# controller5Teensy.net
KiCad netlist of a schematic drawn in EAGLE
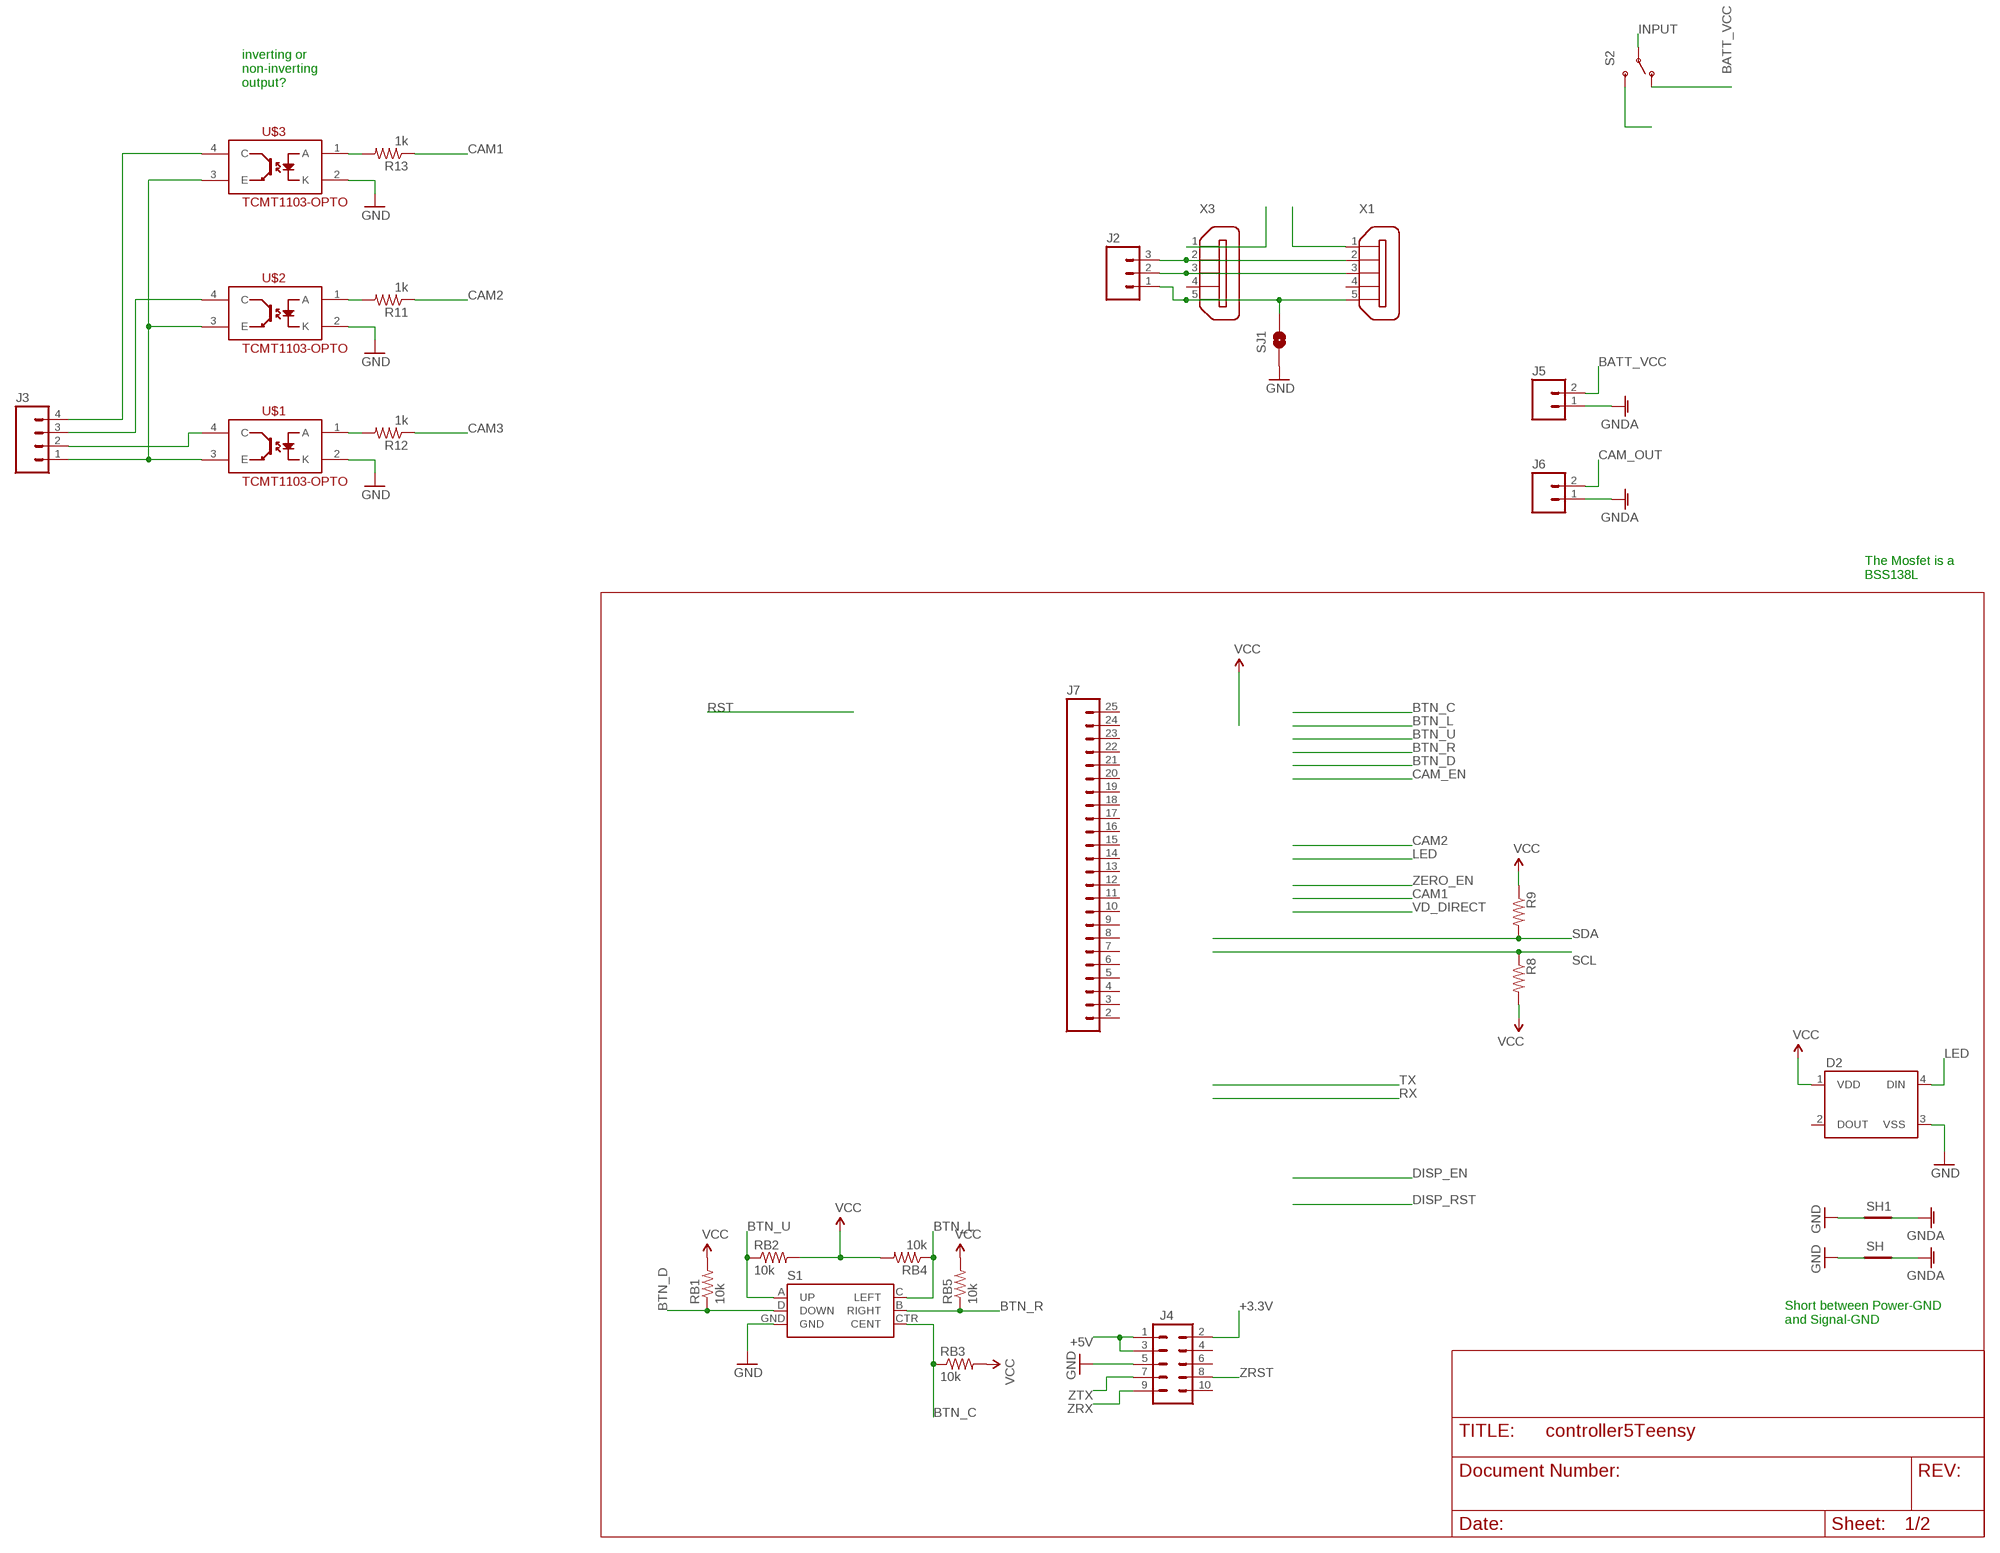
[diagram p0: schematic, sheet 1]
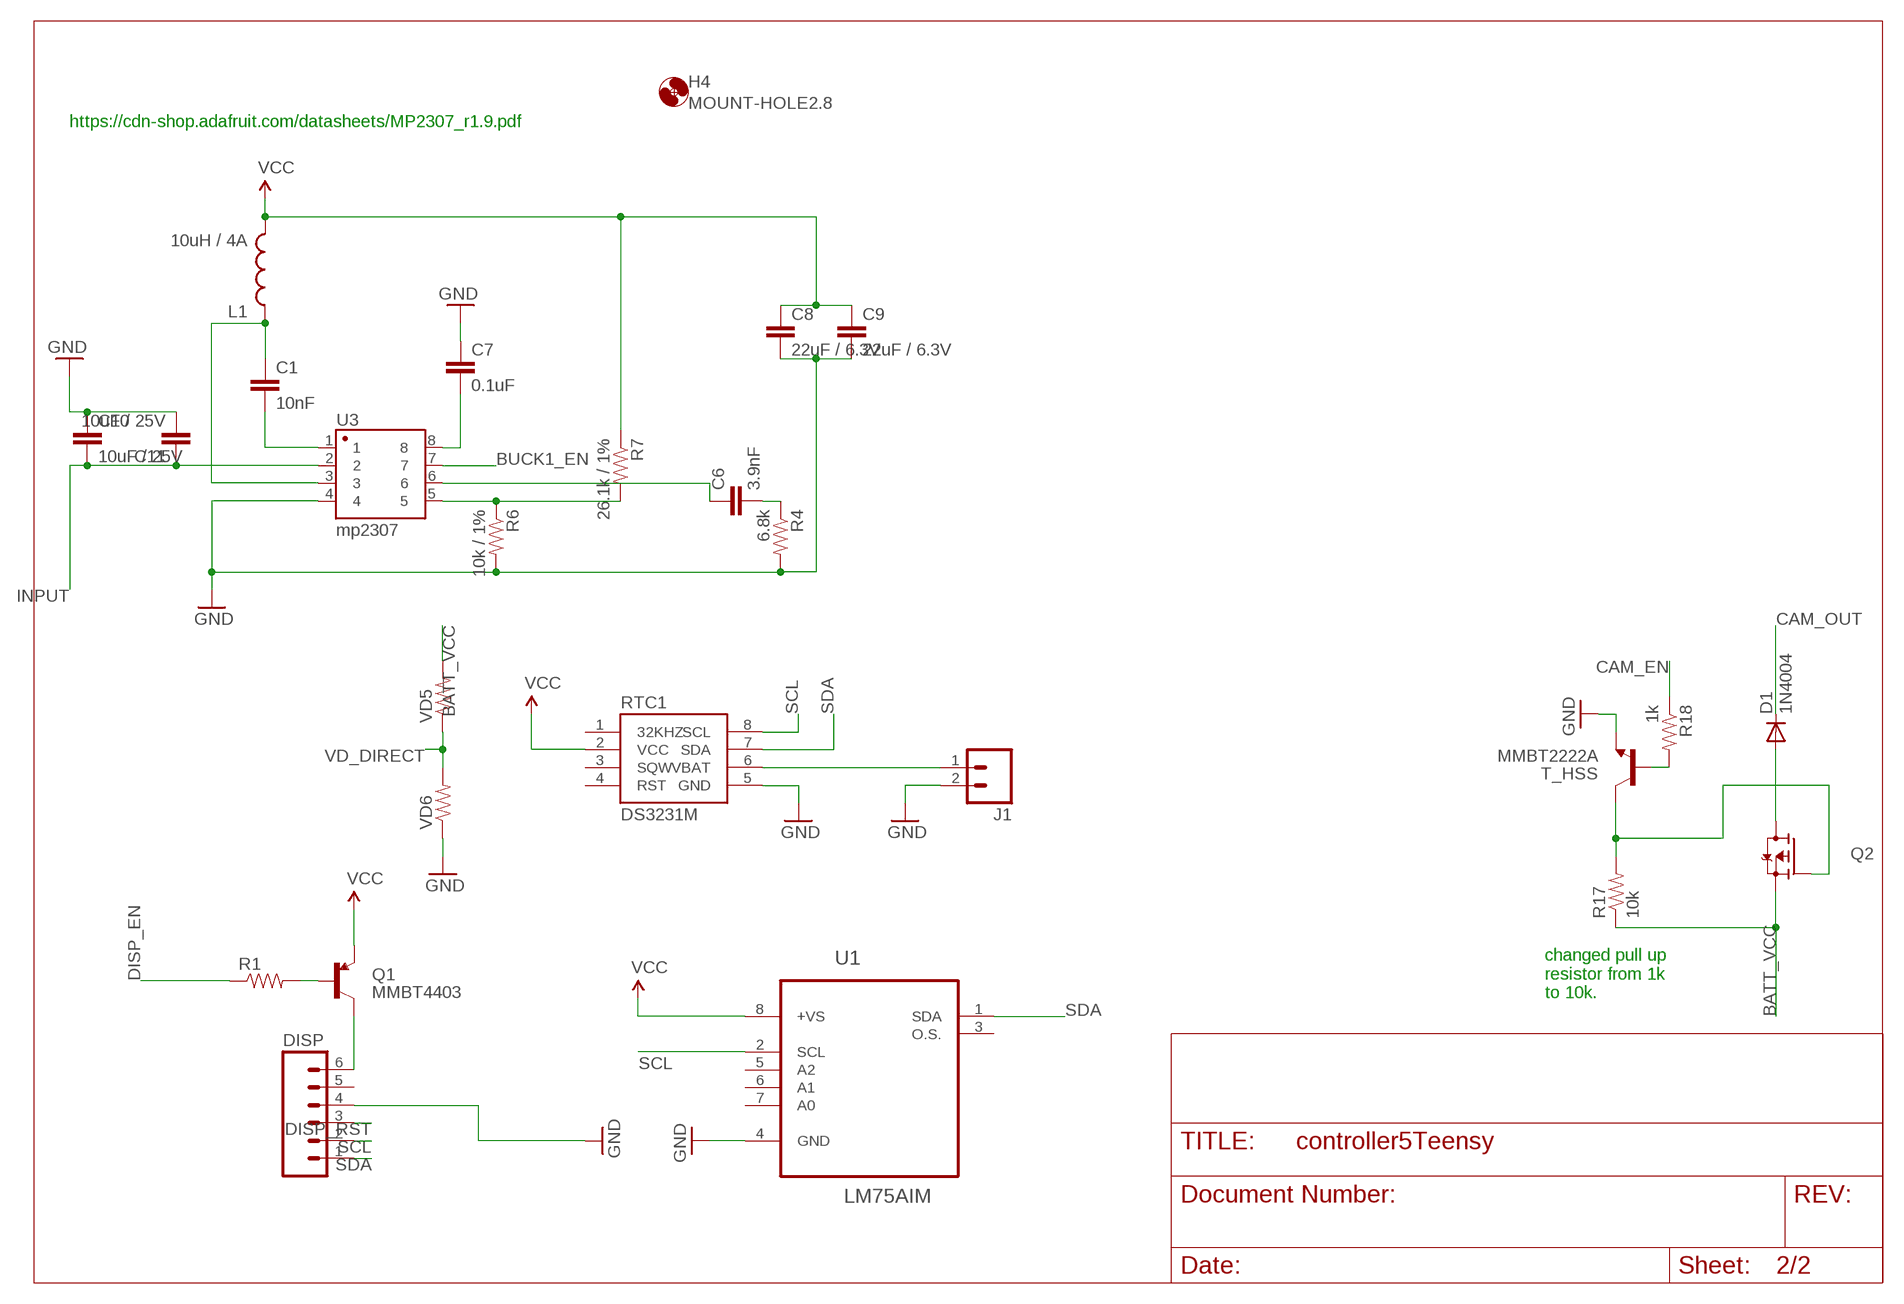
[diagram p1: schematic, sheet 2]

(export (version "E")
  (design (tool "Eeschema 10.0.6"))
  (components
    (comp (ref "D2")
      (value "WS2812B")
      (footprint "eagle-import:WS2812B")
      (libsource (lib "eagle-import") (part "WS2812B"))
    )
    (comp (ref "J2")
      (value "M03LOCK")
      (footprint "eagle-import:1X03_LOCK")
      (libsource (lib "eagle-import") (part "M03LOCK"))
    )
    (comp (ref "J3")
      (value "M04LOCK")
      (footprint "eagle-import:1X04_LOCK")
      (libsource (lib "eagle-import") (part "M04LOCK"))
    )
    (comp (ref "J4")
      (value "M05X2NO_SILK")
      (footprint "eagle-import:2X5_NOSILK")
      (libsource (lib "eagle-import") (part "M05X2NO_SILK"))
    )
    (comp (ref "J5")
      (value "M023.5MM_LOCK")
      (footprint "eagle-import:SCREWTERMINAL-3.5MM-2_LOCK")
      (libsource (lib "eagle-import") (part "M023.5MM_LOCK"))
    )
    (comp (ref "J6")
      (value "M023.5MM_LOCK")
      (footprint "eagle-import:SCREWTERMINAL-3.5MM-2_LOCK")
      (libsource (lib "eagle-import") (part "M023.5MM_LOCK"))
    )
    (comp (ref "J7")
      (value "M24")
      (footprint "eagle-import:1X24")
      (libsource (lib "eagle-import") (part "M24"))
    )
    (comp (ref "R8")
      (value "RESISTOR1206")
      (footprint "eagle-import:1206")
      (libsource (lib "eagle-import") (part "RESISTOR1206"))
    )
    (comp (ref "R9")
      (value "RESISTOR1206")
      (footprint "eagle-import:1206")
      (libsource (lib "eagle-import") (part "RESISTOR1206"))
    )
    (comp (ref "R11")
      (value "1k")
      (footprint "eagle-import:1206")
      (libsource (lib "eagle-import") (part "SparkFun-Resistors_RESISTOR1206"))
    )
    (comp (ref "R12")
      (value "1k")
      (footprint "eagle-import:1206")
      (libsource (lib "eagle-import") (part "SparkFun-Resistors_RESISTOR1206"))
    )
    (comp (ref "R13")
      (value "1k")
      (footprint "eagle-import:1206")
      (libsource (lib "eagle-import") (part "SparkFun-Resistors_RESISTOR1206"))
    )
    (comp (ref "RB1")
      (value "10k")
      (footprint "eagle-import:1206")
      (libsource (lib "eagle-import") (part "SparkFun-Resistors_RESISTOR1206"))
    )
    (comp (ref "RB2")
      (value "10k")
      (footprint "eagle-import:1206")
      (libsource (lib "eagle-import") (part "SparkFun-Resistors_RESISTOR1206"))
    )
    (comp (ref "RB3")
      (value "10k")
      (footprint "eagle-import:1206")
      (libsource (lib "eagle-import") (part "SparkFun-Resistors_RESISTOR1206"))
    )
    (comp (ref "RB4")
      (value "10k")
      (footprint "eagle-import:1206")
      (libsource (lib "eagle-import") (part "SparkFun-Resistors_RESISTOR1206"))
    )
    (comp (ref "RB5")
      (value "10k")
      (footprint "eagle-import:1206")
      (libsource (lib "eagle-import") (part "SparkFun-Resistors_RESISTOR1206"))
    )
    (comp (ref "S1")
      (value "JOYSTICK_MINI")
      (footprint "eagle-import:JOYSTICK_MINI")
      (libsource (lib "eagle-import") (part "JOYSTICK_MINI"))
    )
    (comp (ref "S2")
      (value "SWITCH-SPDTPTH_LOCK")
      (footprint "eagle-import:SWITCH-SPDT_LOCK.007S")
      (libsource (lib "eagle-import") (part "SWITCH-SPDTPTH_LOCK"))
    )
    (comp (ref "SH")
      (value "SHORT-HT5")
      (footprint "eagle-import:SHORT_TOP-50")
      (libsource (lib "eagle-import") (part "SHORT-HT5"))
    )
    (comp (ref "SH1")
      (value "SHORT-HT5")
      (footprint "eagle-import:SHORT_TOP-50")
      (libsource (lib "eagle-import") (part "SHORT-HT5"))
    )
    (comp (ref "SJ1")
      (value "SOLDERJUMPERNO")
      (footprint "eagle-import:SJ_2S-NO")
      (libsource (lib "eagle-import") (part "SOLDERJUMPERNO"))
    )
    (comp (ref "U$1")
      (value "TCMT1103-OPTO")
      (footprint "eagle-import:SSOP-4")
      (libsource (lib "eagle-import") (part "TCMT1103-OPTO"))
    )
    (comp (ref "U$2")
      (value "TCMT1103-OPTO")
      (footprint "eagle-import:SSOP-4")
      (libsource (lib "eagle-import") (part "TCMT1103-OPTO"))
    )
    (comp (ref "U$3")
      (value "TCMT1103-OPTO")
      (footprint "eagle-import:SSOP-4")
      (libsource (lib "eagle-import") (part "TCMT1103-OPTO"))
    )
    (comp (ref "X1")
      (value "ZX62D-B-5PA8")
      (footprint "eagle-import:ZX62D-B-5PA8")
      (fields (field (name "MF") "Hirose"))
      (libsource (lib "eagle-import") (part "ZX62D-B-5PA8"))
    )
    (comp (ref "X3")
      (value "ZX62D-B-5PA8")
      (footprint "eagle-import:ZX62D-B-5PA8")
      (fields (field (name "MF") "Hirose"))
      (libsource (lib "eagle-import") (part "ZX62D-B-5PA8"))
    )
    (comp (ref "C1")
      (value "10nF")
      (footprint "eagle-import:1206")
      (libsource (lib "eagle-import") (part "CAP1206"))
    )
    (comp (ref "C6")
      (value "3.9nF")
      (footprint "eagle-import:1206")
      (libsource (lib "eagle-import") (part "CAP1206"))
    )
    (comp (ref "C7")
      (value "0.1uF")
      (footprint "eagle-import:1206")
      (libsource (lib "eagle-import") (part "CAP1206"))
    )
    (comp (ref "C8")
      (value "22uF / 6.3V")
      (footprint "eagle-import:1206")
      (libsource (lib "eagle-import") (part "CAP1206"))
    )
    (comp (ref "C9")
      (value "22uF / 6.3V")
      (footprint "eagle-import:1206")
      (libsource (lib "eagle-import") (part "CAP1206"))
    )
    (comp (ref "C10")
      (value "10uF / 25V")
      (footprint "eagle-import:1206")
      (libsource (lib "eagle-import") (part "CAP1206"))
    )
    (comp (ref "C11")
      (value "10uF / 25V")
      (footprint "eagle-import:1206")
      (libsource (lib "eagle-import") (part "CAP1206"))
    )
    (comp (ref "D1")
      (value "1N4004")
      (footprint "eagle-import:DO41-10")
      (libsource (lib "eagle-import") (part "1N4004"))
    )
    (comp (ref "DISP")
      (value "M06FEMALE_LOCK")
      (footprint "eagle-import:1X06_FEMALE_LOCK.010")
      (libsource (lib "eagle-import") (part "M06FEMALE_LOCK"))
    )
    (comp (ref "H4")
      (value "MOUNT-HOLE2.8")
      (footprint "eagle-import:2,8")
      (libsource (lib "eagle-import") (part "MOUNT-HOLE2.8"))
    )
    (comp (ref "J1")
      (value "M02LOCK_LONGPADS")
      (footprint "eagle-import:1X02_LOCK_LONGPADS")
      (libsource (lib "eagle-import") (part "M02LOCK_LONGPADS"))
    )
    (comp (ref "L1")
      (value "10uH / 4A")
      (footprint "eagle-import:SDR0403")
      (libsource (lib "eagle-import") (part "INDUCTORSDR0403-560KL"))
    )
    (comp (ref "Q1")
      (value "MMBT4403")
      (footprint "eagle-import:SOT23-3")
      (libsource (lib "eagle-import") (part "TRANSISTOR_PNPMMBT4403"))
    )
    (comp (ref "Q2")
      (value "FDD4141TO252")
      (footprint "eagle-import:TO252")
      (libsource (lib "eagle-import") (part "FDD4141TO252"))
    )
    (comp (ref "R1")
      (value "RESISTOR1206")
      (footprint "eagle-import:1206")
      (libsource (lib "eagle-import") (part "SparkFun-Resistors_RESISTOR1206"))
    )
    (comp (ref "R4")
      (value "6.8k")
      (footprint "eagle-import:1206")
      (libsource (lib "eagle-import") (part "SparkFun-Resistors_RESISTOR1206"))
    )
    (comp (ref "R6")
      (value "10k / 1%")
      (footprint "eagle-import:1206")
      (libsource (lib "eagle-import") (part "SparkFun-Resistors_RESISTOR1206"))
    )
    (comp (ref "R7")
      (value "26.1k / 1%")
      (footprint "eagle-import:1206")
      (libsource (lib "eagle-import") (part "SparkFun-Resistors_RESISTOR1206"))
    )
    (comp (ref "R17")
      (value "10k")
      (footprint "eagle-import:1206")
      (libsource (lib "eagle-import") (part "SparkFun-Resistors_RESISTOR1206"))
    )
    (comp (ref "R18")
      (value "1k")
      (footprint "eagle-import:1206")
      (libsource (lib "eagle-import") (part "SparkFun-Resistors_RESISTOR1206"))
    )
    (comp (ref "RTC1")
      (value "DS3231M")
      (footprint "eagle-import:SOIC8")
      (libsource (lib "eagle-import") (part "DS3231M"))
    )
    (comp (ref "T_HSS")
      (value "MMBT2222A")
      (footprint "eagle-import:SOT23-3")
      (libsource (lib "eagle-import") (part "TRANSISTOR_NPNMMBT2222A"))
    )
    (comp (ref "U1")
      (value "LM75AIM")
      (footprint "eagle-import:SOIC127P620X175-8N")
      (libsource (lib "eagle-import") (part "LM75AIM"))
    )
    (comp (ref "U3")
      (value "mp2307")
      (footprint "eagle-import:SO08-UNIVERSAL")
      (libsource (lib "eagle-import") (part "GENERIC-SOIC8"))
    )
    (comp (ref "VD5")
      (value "RESISTOR1206")
      (footprint "eagle-import:1206")
      (libsource (lib "eagle-import") (part "RESISTOR1206"))
    )
    (comp (ref "VD6")
      (value "RESISTOR1206")
      (footprint "eagle-import:1206")
      (libsource (lib "eagle-import") (part "RESISTOR1206"))
    )
  )
  (nets
    (net (code "1") (name "+3.3V") (class "Default")
      (node (ref "J4") (pin "2") (pinfunction "2_2") (pintype "passive"))
    )
    (net (code "2") (name "+5V") (class "Default")
      (node (ref "J4") (pin "1") (pinfunction "1_1") (pintype "passive"))
      (node (ref "J4") (pin "3") (pinfunction "3_3") (pintype "passive"))
    )
    (net (code "3") (name "BATT_VCC") (class "Default")
      (node (ref "J5") (pin "2") (pinfunction "2_2") (pintype "passive"))
      (node (ref "Q2") (pin "2") (pinfunction "S_2") (pintype "passive"))
      (node (ref "R17") (pin "1") (pinfunction "1_1") (pintype "passive"))
      (node (ref "S2") (pin "1") (pinfunction "O_1") (pintype "passive"))
      (node (ref "VD5") (pin "2") (pinfunction "2_2") (pintype "passive"))
    )
    (net (code "4") (name "BTN_C") (class "Default")
      (node (ref "RB3") (pin "1") (pinfunction "1_1") (pintype "passive"))
      (node (ref "S1") (pin "CTR") (pinfunction "CENT_CTR") (pintype "bidirectional"))
    )
    (net (code "5") (name "BTN_D") (class "Default")
      (node (ref "RB1") (pin "1") (pinfunction "1_1") (pintype "passive"))
      (node (ref "S1") (pin "D") (pinfunction "DOWN_D") (pintype "bidirectional"))
    )
    (net (code "6") (name "BTN_L") (class "Default")
      (node (ref "RB4") (pin "1") (pinfunction "1_1") (pintype "passive"))
      (node (ref "S1") (pin "C") (pinfunction "LEFT_C") (pintype "bidirectional"))
    )
    (net (code "7") (name "BTN_R") (class "Default")
      (node (ref "RB5") (pin "1") (pinfunction "1_1") (pintype "passive"))
      (node (ref "S1") (pin "B") (pinfunction "RIGHT_B") (pintype "bidirectional"))
    )
    (net (code "8") (name "BTN_U") (class "Default")
      (node (ref "RB2") (pin "1") (pinfunction "1_1") (pintype "passive"))
      (node (ref "S1") (pin "A") (pinfunction "UP_A") (pintype "bidirectional"))
    )
    (net (code "9") (name "BUCK1_EN") (class "Default")
      (node (ref "U3") (pin "7") (pinfunction "7_7") (pintype "bidirectional"))
    )
    (net (code "10") (name "CAM1") (class "Default")
      (node (ref "R13") (pin "1") (pinfunction "1_1") (pintype "passive"))
    )
    (net (code "11") (name "CAM2") (class "Default")
      (node (ref "R11") (pin "1") (pinfunction "1_1") (pintype "passive"))
    )
    (net (code "12") (name "CAM3") (class "Default")
      (node (ref "R12") (pin "1") (pinfunction "1_1") (pintype "passive"))
    )
    (net (code "13") (name "CAM_EN") (class "Default")
      (node (ref "R18") (pin "1") (pinfunction "1_1") (pintype "passive"))
    )
    (net (code "14") (name "CAM_OUT") (class "Default")
      (node (ref "D1") (pin "C") (pinfunction "C_C") (pintype "passive"))
      (node (ref "J6") (pin "2") (pinfunction "2_2") (pintype "passive"))
    )
    (net (code "15") (name "DISP_EN") (class "Default")
      (node (ref "R1") (pin "1") (pinfunction "1_1") (pintype "passive"))
    )
    (net (code "16") (name "DISP_RST") (class "Default")
      (node (ref "DISP") (pin "3") (pinfunction "3_3") (pintype "passive"))
    )
    (net (code "17") (name "GND") (class "Default")
      (node (ref "C10") (pin "1") (pinfunction "1_1") (pintype "passive"))
      (node (ref "C11") (pin "2") (pinfunction "2_2") (pintype "passive"))
      (node (ref "C7") (pin "1") (pinfunction "1_1") (pintype "passive"))
      (node (ref "C8") (pin "2") (pinfunction "2_2") (pintype "passive"))
      (node (ref "C9") (pin "2") (pinfunction "2_2") (pintype "passive"))
      (node (ref "D2") (pin "3") (pinfunction "VSS_3") (pintype "power_in"))
      (node (ref "DISP") (pin "4") (pinfunction "4_4") (pintype "passive"))
      (node (ref "J1") (pin "2") (pinfunction "2_2") (pintype "passive"))
      (node (ref "J4") (pin "5") (pinfunction "5_5") (pintype "passive"))
      (node (ref "R4") (pin "2") (pinfunction "2_2") (pintype "passive"))
      (node (ref "R6") (pin "2") (pinfunction "2_2") (pintype "passive"))
      (node (ref "RTC1") (pin "5") (pinfunction "GND_5") (pintype "power_in"))
      (node (ref "S1") (pin "GND") (pinfunction "GND_GND") (pintype "bidirectional"))
      (node (ref "SH") (pin "1") (pinfunction "P$1_1") (pintype "bidirectional"))
      (node (ref "SH1") (pin "1") (pinfunction "P$1_1") (pintype "bidirectional"))
      (node (ref "SJ1") (pin "1") (pinfunction "1_1") (pintype "passive"))
      (node (ref "T_HSS") (pin "2") (pinfunction "E_2") (pintype "passive"))
      (node (ref "U$1") (pin "2") (pinfunction "K_2") (pintype "bidirectional"))
      (node (ref "U$2") (pin "2") (pinfunction "K_2") (pintype "bidirectional"))
      (node (ref "U$3") (pin "2") (pinfunction "K_2") (pintype "bidirectional"))
      (node (ref "U1") (pin "4") (pinfunction "GND_4") (pintype "passive"))
      (node (ref "U3") (pin "4") (pinfunction "4_4") (pintype "bidirectional"))
      (node (ref "VD6") (pin "1") (pinfunction "1_1") (pintype "passive"))
    )
    (net (code "18") (name "GNDA") (class "Default")
      (node (ref "J5") (pin "1") (pinfunction "1_1") (pintype "passive"))
      (node (ref "J6") (pin "1") (pinfunction "1_1") (pintype "passive"))
      (node (ref "SH") (pin "2") (pinfunction "P$2_2") (pintype "bidirectional"))
      (node (ref "SH1") (pin "2") (pinfunction "P$2_2") (pintype "bidirectional"))
    )
    (net (code "19") (name "INPUT") (class "Default")
      (node (ref "C10") (pin "2") (pinfunction "2_2") (pintype "passive"))
      (node (ref "C11") (pin "1") (pinfunction "1_1") (pintype "passive"))
      (node (ref "S2") (pin "2") (pinfunction "P_2") (pintype "passive"))
      (node (ref "U3") (pin "2") (pinfunction "2_2") (pintype "bidirectional"))
    )
    (net (code "20") (name "LED") (class "Default")
      (node (ref "D2") (pin "4") (pinfunction "DIN_4") (pintype "input"))
    )
    (net (code "21") (name "Net-(C1-Pad2)") (class "Default")
      (node (ref "C1") (pin "2") (pinfunction "2_2") (pintype "passive"))
      (node (ref "U3") (pin "1") (pinfunction "1_1") (pintype "bidirectional"))
    )
    (net (code "22") (name "Net-(C6-Pad1)") (class "Default")
      (node (ref "C6") (pin "1") (pinfunction "1_1") (pintype "passive"))
      (node (ref "U3") (pin "6") (pinfunction "6_6") (pintype "bidirectional"))
    )
    (net (code "23") (name "Net-(C6-Pad2)") (class "Default")
      (node (ref "C6") (pin "2") (pinfunction "2_2") (pintype "passive"))
      (node (ref "R4") (pin "1") (pinfunction "1_1") (pintype "passive"))
    )
    (net (code "24") (name "Net-(C7-Pad2)") (class "Default")
      (node (ref "C7") (pin "2") (pinfunction "2_2") (pintype "passive"))
      (node (ref "U3") (pin "8") (pinfunction "8_8") (pintype "bidirectional"))
    )
    (net (code "25") (name "Net-(J2-Pad1)") (class "Default")
      (node (ref "J2") (pin "1") (pinfunction "1_1") (pintype "passive"))
      (node (ref "SJ1") (pin "2") (pinfunction "2_2") (pintype "passive"))
      (node (ref "X1") (pin "5") (pinfunction "5_5") (pintype "passive"))
      (node (ref "X3") (pin "5") (pinfunction "5_5") (pintype "passive"))
    )
    (net (code "26") (name "Net-(J2-Pad2)") (class "Default")
      (node (ref "J2") (pin "2") (pinfunction "2_2") (pintype "passive"))
      (node (ref "X1") (pin "3") (pinfunction "3_3") (pintype "passive"))
      (node (ref "X3") (pin "3") (pinfunction "3_3") (pintype "passive"))
    )
    (net (code "27") (name "Net-(J2-Pad3)") (class "Default")
      (node (ref "J2") (pin "3") (pinfunction "3_3") (pintype "passive"))
      (node (ref "X1") (pin "2") (pinfunction "2_2") (pintype "passive"))
      (node (ref "X3") (pin "2") (pinfunction "2_2") (pintype "passive"))
    )
    (net (code "28") (name "Net-(L1-1)") (class "Default")
      (node (ref "C1") (pin "1") (pinfunction "1_1") (pintype "passive"))
      (node (ref "L1") (pin "P$1") (pinfunction "1_P$1") (pintype "passive"))
      (node (ref "U3") (pin "3") (pinfunction "3_3") (pintype "bidirectional"))
    )
    (net (code "29") (name "Net-(Q1-B)") (class "Default")
      (node (ref "Q1") (pin "1") (pinfunction "B_1") (pintype "passive"))
      (node (ref "R1") (pin "2") (pinfunction "2_2") (pintype "passive"))
    )
    (net (code "30") (name "Net-(Q1-C)") (class "Default")
      (node (ref "DISP") (pin "6") (pinfunction "6_6") (pintype "passive"))
      (node (ref "Q1") (pin "3") (pinfunction "C_3") (pintype "passive"))
    )
    (net (code "31") (name "Net-(Q2-D)") (class "Default")
      (node (ref "D1") (pin "A") (pinfunction "A_A") (pintype "passive"))
      (node (ref "Q2") (pin "3") (pinfunction "D_3") (pintype "passive"))
    )
    (net (code "32") (name "Net-(Q2-G)") (class "Default")
      (node (ref "Q2") (pin "1") (pinfunction "G_1") (pintype "passive"))
      (node (ref "R17") (pin "2") (pinfunction "2_2") (pintype "passive"))
      (node (ref "T_HSS") (pin "3") (pinfunction "C_3") (pintype "passive"))
    )
    (net (code "33") (name "Net-(R6-Pad1)") (class "Default")
      (node (ref "R6") (pin "1") (pinfunction "1_1") (pintype "passive"))
      (node (ref "R7") (pin "2") (pinfunction "2_2") (pintype "passive"))
      (node (ref "U3") (pin "5") (pinfunction "5_5") (pintype "bidirectional"))
    )
    (net (code "34") (name "Net-(RTC1-VBAT)") (class "Default")
      (node (ref "J1") (pin "1") (pinfunction "1_1") (pintype "passive"))
      (node (ref "RTC1") (pin "6") (pinfunction "VBAT_6") (pintype "power_in"))
    )
    (net (code "35") (name "Net-(T_HSS-B)") (class "Default")
      (node (ref "R18") (pin "2") (pinfunction "2_2") (pintype "passive"))
      (node (ref "T_HSS") (pin "1") (pinfunction "B_1") (pintype "passive"))
    )
    (net (code "36") (name "Net-(U$1-A)") (class "Default")
      (node (ref "R12") (pin "2") (pinfunction "2_2") (pintype "passive"))
      (node (ref "U$1") (pin "1") (pinfunction "A_1") (pintype "bidirectional"))
    )
    (net (code "37") (name "Net-(U$1-C)") (class "Default")
      (node (ref "J3") (pin "2") (pinfunction "2_2") (pintype "passive"))
      (node (ref "U$1") (pin "4") (pinfunction "C_4") (pintype "bidirectional"))
    )
    (net (code "38") (name "Net-(U$1-E)") (class "Default")
      (node (ref "J3") (pin "1") (pinfunction "1_1") (pintype "passive"))
      (node (ref "U$1") (pin "3") (pinfunction "E_3") (pintype "bidirectional"))
      (node (ref "U$2") (pin "3") (pinfunction "E_3") (pintype "bidirectional"))
      (node (ref "U$3") (pin "3") (pinfunction "E_3") (pintype "bidirectional"))
    )
    (net (code "39") (name "Net-(U$2-A)") (class "Default")
      (node (ref "R11") (pin "2") (pinfunction "2_2") (pintype "passive"))
      (node (ref "U$2") (pin "1") (pinfunction "A_1") (pintype "bidirectional"))
    )
    (net (code "40") (name "Net-(U$2-C)") (class "Default")
      (node (ref "J3") (pin "3") (pinfunction "3_3") (pintype "passive"))
      (node (ref "U$2") (pin "4") (pinfunction "C_4") (pintype "bidirectional"))
    )
    (net (code "41") (name "Net-(U$3-A)") (class "Default")
      (node (ref "R13") (pin "2") (pinfunction "2_2") (pintype "passive"))
      (node (ref "U$3") (pin "1") (pinfunction "A_1") (pintype "bidirectional"))
    )
    (net (code "42") (name "Net-(U$3-C)") (class "Default")
      (node (ref "J3") (pin "4") (pinfunction "4_4") (pintype "passive"))
      (node (ref "U$3") (pin "4") (pinfunction "C_4") (pintype "bidirectional"))
    )
    (net (code "45") (name "SCL") (class "Default")
      (node (ref "DISP") (pin "2") (pinfunction "2_2") (pintype "passive"))
      (node (ref "R8") (pin "1") (pinfunction "1_1") (pintype "passive"))
      (node (ref "RTC1") (pin "8") (pinfunction "SCL_8") (pintype "bidirectional"))
      (node (ref "U1") (pin "2") (pinfunction "SCL_2") (pintype "input"))
    )
    (net (code "46") (name "SDA") (class "Default")
      (node (ref "DISP") (pin "1") (pinfunction "1_1") (pintype "passive"))
      (node (ref "R9") (pin "2") (pinfunction "2_2") (pintype "passive"))
      (node (ref "RTC1") (pin "7") (pinfunction "SDA_7") (pintype "bidirectional"))
      (node (ref "U1") (pin "1") (pinfunction "SDA_1") (pintype "bidirectional"))
    )
    (net (code "48") (name "VCC") (class "Default")
      (node (ref "C8") (pin "1") (pinfunction "1_1") (pintype "passive"))
      (node (ref "C9") (pin "1") (pinfunction "1_1") (pintype "passive"))
      (node (ref "D2") (pin "1") (pinfunction "VDD_1") (pintype "power_in"))
      (node (ref "L1") (pin "P$2") (pinfunction "2_P$2") (pintype "passive"))
      (node (ref "Q1") (pin "2") (pinfunction "E_2") (pintype "passive"))
      (node (ref "R7") (pin "1") (pinfunction "1_1") (pintype "passive"))
      (node (ref "R8") (pin "2") (pinfunction "2_2") (pintype "passive"))
      (node (ref "R9") (pin "1") (pinfunction "1_1") (pintype "passive"))
      (node (ref "RB1") (pin "2") (pinfunction "2_2") (pintype "passive"))
      (node (ref "RB2") (pin "2") (pinfunction "2_2") (pintype "passive"))
      (node (ref "RB3") (pin "2") (pinfunction "2_2") (pintype "passive"))
      (node (ref "RB4") (pin "2") (pinfunction "2_2") (pintype "passive"))
      (node (ref "RB5") (pin "2") (pinfunction "2_2") (pintype "passive"))
      (node (ref "RTC1") (pin "2") (pinfunction "VCC_2") (pintype "power_in"))
      (node (ref "U1") (pin "8") (pinfunction "+VS_8") (pintype "power_in"))
    )
    (net (code "49") (name "VD_DIRECT") (class "Default")
      (node (ref "VD5") (pin "1") (pinfunction "1_1") (pintype "passive"))
      (node (ref "VD6") (pin "2") (pinfunction "2_2") (pintype "passive"))
    )
    (net (code "51") (name "ZRST") (class "Default")
      (node (ref "J4") (pin "8") (pinfunction "8_8") (pintype "passive"))
    )
    (net (code "52") (name "ZRX") (class "Default")
      (node (ref "J4") (pin "9") (pinfunction "9_9") (pintype "passive"))
    )
    (net (code "53") (name "ZTX") (class "Default")
      (node (ref "J4") (pin "7") (pinfunction "7_7") (pintype "passive"))
    )
    (net (code "54") (name "unconnected-(D2-DOUT-Pad2)") (class "Default")
      (node (ref "D2") (pin "2") (pinfunction "DOUT_2") (pintype "output"))
    )
    (net (code "55") (name "unconnected-(DISP-Pad5)") (class "Default")
      (node (ref "DISP") (pin "5") (pinfunction "5_5") (pintype "passive"))
    )
    (net (code "56") (name "unconnected-(J4-Pad4)") (class "Default")
      (node (ref "J4") (pin "4") (pinfunction "4_4") (pintype "passive"))
    )
    (net (code "57") (name "unconnected-(J4-Pad6)") (class "Default")
      (node (ref "J4") (pin "6") (pinfunction "6_6") (pintype "passive"))
    )
    (net (code "58") (name "unconnected-(J4-Pad10)") (class "Default")
      (node (ref "J4") (pin "10") (pinfunction "10_10") (pintype "passive"))
    )
    (net (code "59") (name "unconnected-(J7-Pad2)") (class "Default")
      (node (ref "J7") (pin "2") (pinfunction "2_2") (pintype "passive"))
    )
    (net (code "60") (name "unconnected-(J7-Pad3)") (class "Default")
      (node (ref "J7") (pin "3") (pinfunction "3_3") (pintype "passive"))
    )
    (net (code "61") (name "unconnected-(J7-Pad4)") (class "Default")
      (node (ref "J7") (pin "4") (pinfunction "4_4") (pintype "passive"))
    )
    (net (code "62") (name "unconnected-(J7-Pad5)") (class "Default")
      (node (ref "J7") (pin "5") (pinfunction "5_5") (pintype "passive"))
    )
    (net (code "63") (name "unconnected-(J7-Pad6)") (class "Default")
      (node (ref "J7") (pin "6") (pinfunction "6_6") (pintype "passive"))
    )
    (net (code "64") (name "unconnected-(J7-Pad7)") (class "Default")
      (node (ref "J7") (pin "7") (pinfunction "7_7") (pintype "passive"))
    )
    (net (code "65") (name "unconnected-(J7-Pad8)") (class "Default")
      (node (ref "J7") (pin "8") (pinfunction "8_8") (pintype "passive"))
    )
    (net (code "66") (name "unconnected-(J7-Pad9)") (class "Default")
      (node (ref "J7") (pin "9") (pinfunction "9_9") (pintype "passive"))
    )
    (net (code "67") (name "unconnected-(J7-Pad10)") (class "Default")
      (node (ref "J7") (pin "10") (pinfunction "10_10") (pintype "passive"))
    )
    (net (code "68") (name "unconnected-(J7-Pad11)") (class "Default")
      (node (ref "J7") (pin "11") (pinfunction "11_11") (pintype "passive"))
    )
    (net (code "69") (name "unconnected-(J7-Pad12)") (class "Default")
      (node (ref "J7") (pin "12") (pinfunction "12_12") (pintype "passive"))
    )
    (net (code "70") (name "unconnected-(J7-Pad13)") (class "Default")
      (node (ref "J7") (pin "13") (pinfunction "13_13") (pintype "passive"))
    )
    (net (code "71") (name "unconnected-(J7-Pad14)") (class "Default")
      (node (ref "J7") (pin "14") (pinfunction "14_14") (pintype "passive"))
    )
    (net (code "72") (name "unconnected-(J7-Pad15)") (class "Default")
      (node (ref "J7") (pin "15") (pinfunction "15_15") (pintype "passive"))
    )
    (net (code "73") (name "unconnected-(J7-Pad16)") (class "Default")
      (node (ref "J7") (pin "16") (pinfunction "16_16") (pintype "passive"))
    )
    (net (code "74") (name "unconnected-(J7-Pad17)") (class "Default")
      (node (ref "J7") (pin "17") (pinfunction "17_17") (pintype "passive"))
    )
    (net (code "75") (name "unconnected-(J7-Pad18)") (class "Default")
      (node (ref "J7") (pin "18") (pinfunction "18_18") (pintype "passive"))
    )
    (net (code "76") (name "unconnected-(J7-Pad19)") (class "Default")
      (node (ref "J7") (pin "19") (pinfunction "19_19") (pintype "passive"))
    )
    (net (code "77") (name "unconnected-(J7-Pad20)") (class "Default")
      (node (ref "J7") (pin "20") (pinfunction "20_20") (pintype "passive"))
    )
    (net (code "78") (name "unconnected-(J7-Pad21)") (class "Default")
      (node (ref "J7") (pin "21") (pinfunction "21_21") (pintype "passive"))
    )
    (net (code "79") (name "unconnected-(J7-Pad22)") (class "Default")
      (node (ref "J7") (pin "22") (pinfunction "22_22") (pintype "passive"))
    )
    (net (code "80") (name "unconnected-(J7-Pad23)") (class "Default")
      (node (ref "J7") (pin "23") (pinfunction "23_23") (pintype "passive"))
    )
    (net (code "81") (name "unconnected-(J7-Pad24)") (class "Default")
      (node (ref "J7") (pin "24") (pinfunction "24_24") (pintype "passive"))
    )
    (net (code "82") (name "unconnected-(J7-Pad25)") (class "Default")
      (node (ref "J7") (pin "25") (pinfunction "25_25") (pintype "passive"))
    )
    (net (code "83") (name "unconnected-(RTC1-32KHZ-Pad1)") (class "Default")
      (node (ref "RTC1") (pin "1") (pinfunction "32KHZ_1") (pintype "output"))
    )
    (net (code "84") (name "unconnected-(RTC1-RST-Pad4)") (class "Default")
      (node (ref "RTC1") (pin "4") (pinfunction "RST_4") (pintype "bidirectional"))
    )
    (net (code "85") (name "unconnected-(RTC1-SQW-Pad3)") (class "Default")
      (node (ref "RTC1") (pin "3") (pinfunction "SQW_3") (pintype "output"))
    )
    (net (code "86") (name "unconnected-(S2-S-Pad3)") (class "Default")
      (node (ref "S2") (pin "3") (pinfunction "S_3") (pintype "passive"))
    )
    (net (code "87") (name "unconnected-(U1-A0-Pad7)") (class "Default")
      (node (ref "U1") (pin "7") (pinfunction "A0_7") (pintype "input"))
    )
    (net (code "88") (name "unconnected-(U1-A1-Pad6)") (class "Default")
      (node (ref "U1") (pin "6") (pinfunction "A1_6") (pintype "input"))
    )
    (net (code "89") (name "unconnected-(U1-A2-Pad5)") (class "Default")
      (node (ref "U1") (pin "5") (pinfunction "A2_5") (pintype "input"))
    )
    (net (code "90") (name "unconnected-(U1-O.S.-Pad3)") (class "Default")
      (node (ref "U1") (pin "3") (pinfunction "O.S._3") (pintype "output"))
    )
    (net (code "91") (name "unconnected-(X1-Pad1)") (class "Default")
      (node (ref "X1") (pin "1") (pinfunction "1_1") (pintype "passive"))
    )
    (net (code "92") (name "unconnected-(X1-Pad4)") (class "Default")
      (node (ref "X1") (pin "4") (pinfunction "4_4") (pintype "passive"))
    )
    (net (code "93") (name "unconnected-(X3-Pad1)") (class "Default")
      (node (ref "X3") (pin "1") (pinfunction "1_1") (pintype "passive"))
    )
    (net (code "94") (name "unconnected-(X3-Pad4)") (class "Default")
      (node (ref "X3") (pin "4") (pinfunction "4_4") (pintype "passive"))
    )
  )
)
